# USB-ESP32.net
KiCad netlist of a schematic drawn in Altium Designer
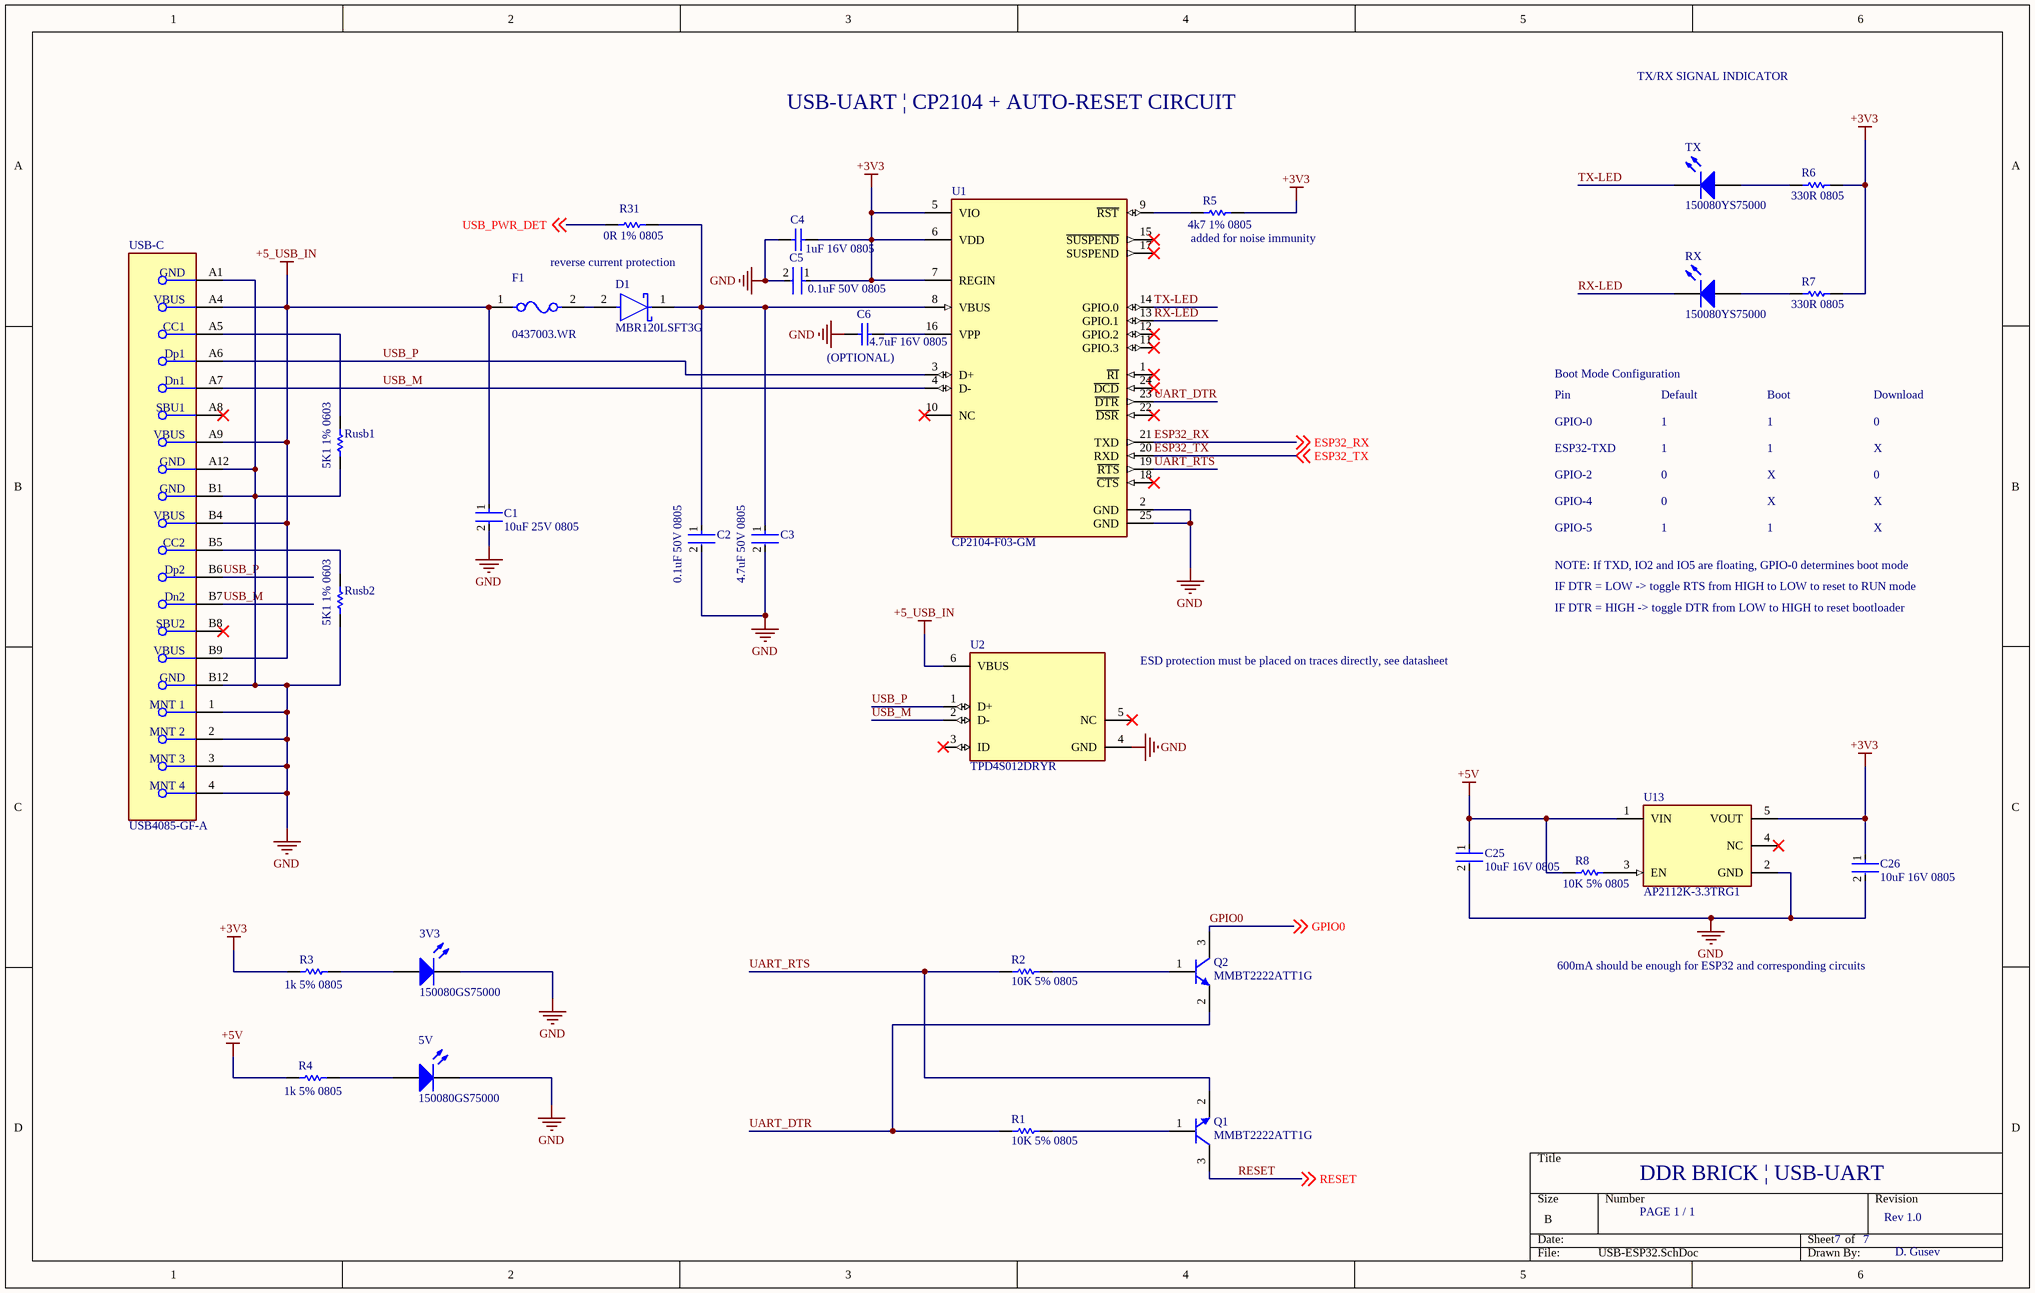
[diagram p0: USB-ESP32.SchDoc]

(export (version "E")
  (design (tool "Eeschema 10.0.6"))
  (components
    (comp (ref "3V3")
      (value "150080GS75000")
      (footprint "0805_A")
      (description "SMD mono-color Chip LED, WL-SMCW, Green")
      (fields (field (name "MANUFACTURER") "Wuerth Elektronik"))
      (libsource (lib "Altium Content Vault") (part "WE-LED_K1A2-2"))
    )
    (comp (ref "5V")
      (value "150080GS75000")
      (footprint "0805_A")
      (description "SMD mono-color Chip LED, WL-SMCW, Green")
      (fields (field (name "MANUFACTURER") "Wuerth Elektronik"))
      (libsource (lib "Altium Content Vault") (part "WE-LED_K1A2-2"))
    )
    (comp (ref "C1")
      (value "10uF 25V 0805")
      (footprint "FP-GRM21B-0_15-IPC_C")
      (description "Chip Multilayer Ceramic Capacitors for General Purpose, 0805, 10uF, X5R, 15%, 10%, 25V")
      (fields (field (name "VOLTAGE") "25V") (field (name "TOLERANCE") "10%"))
      (libsource (lib "Altium Content Vault") (part "b4654b650e69147ec39a6b967a45e02"))
    )
    (comp (ref "C2")
      (value "0.1uF 50V 0805")
      (footprint "FP-C0805C-DN-MFG")
      (description "CAP CER 0.1UF 50V X7R 0805")
      (fields
        (field (name "MANUFACTURER PART NUMBER") "C0805C104K5RACTU")
        (field (name "MANUFACTURER") "KEMET")
      )
      (libsource (lib "Altium Content Vault") (part "b4654b650e69147ec39a6b967a45e02"))
    )
    (comp (ref "C3")
      (value "4.7uF 50V 0805")
      (footprint "FP-C2012-125-MFG")
      (description "CAP CER 4.7UF 50V X5R 0805")
      (fields
        (field (name "TOLERANCE") "10%")
        (field (name "MANUFACTURER PART NUMBER") "C2012X5R1H475K125AB")
      )
      (libsource (lib "Altium Content Vault") (part "11868f565c42a9108669ba33697ecf6"))
    )
    (comp (ref "C4")
      (value "1uF 16V 0805")
      (footprint "CAPC2013X145X50LL20T25")
      (fields (field (name "MANUFACTURER") "Kemet") (field (name "PART NUMBER") "C0805C105K4PACTU"))
      (libsource (lib "Altium Content Vault") (part "CAP"))
    )
    (comp (ref "C5")
      (value "0.1uF 50V 0805")
      (footprint "FP-C0805C-DN-MFG")
      (description "CAP CER 0.1UF 50V X7R 0805")
      (fields
        (field (name "MANUFACTURER PART NUMBER") "C0805C104K5RACTU")
        (field (name "MANUFACTURER") "KEMET")
      )
      (libsource (lib "Altium Content Vault") (part "b4654b650e69147ec39a6b967a45e02"))
    )
    (comp (ref "C6")
      (value "4.7uF 16V 0805")
      (footprint "CAPC2013X140X50LL20T25")
      (fields (field (name "PART NUMBER") "C0805C475K4PACTU") (field (name "MANUFACTURER") "Kemet"))
      (libsource (lib "Altium Content Vault") (part "CAP"))
    )
    (comp (ref "C25")
      (value "10uF 16V 0805")
      (footprint "FP-GRM21B-0_1-IPC_C")
      (description "Chip Multilayer Ceramic Capacitors for General Purpose, 0805, 10uF, X5R, 15%, 10%, 16V")
      (fields (field (name "TOLERANCE") "10%") (field (name "VOLTAGE") "16V"))
      (libsource (lib "Altium Content Vault") (part "b4654b650e69147ec39a6b967a45e02"))
    )
    (comp (ref "C26")
      (value "10uF 16V 0805")
      (footprint "FP-GRM21B-0_1-IPC_C")
      (description "Chip Multilayer Ceramic Capacitors for General Purpose, 0805, 10uF, X5R, 15%, 10%, 16V")
      (fields (field (name "TOLERANCE") "10%") (field (name "VOLTAGE") "16V"))
      (libsource (lib "Altium Content Vault") (part "b4654b650e69147ec39a6b967a45e02"))
    )
    (comp (ref "D1")
      (value "MBR120LSFT3G")
      (footprint "FP-498-MFG")
      (description "DIODE SCHOTTKY 20V 1A SOD123L")
      (libsource (lib "Altium Content Vault") (part "1d6ec82d83fb6aee721767c19dac4b9"))
    )
    (comp (ref "F1")
      (value "0437003.WR")
      (footprint "FP-437-MFG")
      (description "FUSE BRD MNT 3A 32VAC 35VDC 1206")
      (fields
        (field (name "OCTOPART") "https://octopart.com/0437003.wr-littelfuse-8600121")
        (field (name "MANUFACTURER") "Littelfuse Inc")
      )
      (libsource (lib "Altium Content Vault") (part "5bcf9b9f640e542cf0359d10258e979"))
    )
    (comp (ref "Q1")
      (value "MMBT2222ATT1G")
      (footprint "ONSC-SC-75-3-463-01_V")
      (description "General Purpose Transistor, NPN Silicon, 3-Pin SC-75, Pb-Free, Tape and Reel")
      (fields (field (name "MANUFACTURER") "On Semiconductor"))
      (libsource (lib "Altium Content Vault") (part "ONSC-NPN-B1E2C3-3"))
    )
    (comp (ref "Q2")
      (value "MMBT2222ATT1G")
      (footprint "ONSC-SC-75-3-463-01_V")
      (description "General Purpose Transistor, NPN Silicon, 3-Pin SC-75, Pb-Free, Tape and Reel")
      (fields (field (name "MANUFACTURER") "On Semiconductor"))
      (libsource (lib "Altium Content Vault") (part "ONSC-NPN-B1E2C3-3"))
    )
    (comp (ref "R1")
      (value "10K 5% 0805")
      (footprint "RESC2013X60X40ML20T25")
      (fields (field (name "PART NUMBER") "ERA6AEB123V") (field (name "MANUFACTURER") "Panasonic"))
      (libsource (lib "Altium Content Vault") (part "RES"))
    )
    (comp (ref "R2")
      (value "10K 5% 0805")
      (footprint "RESC2013X60X40ML20T25")
      (fields (field (name "PART NUMBER") "ERA6AEB123V") (field (name "MANUFACTURER") "Panasonic"))
      (libsource (lib "Altium Content Vault") (part "RES"))
    )
    (comp (ref "R3")
      (value "1k 5% 0805")
      (footprint "RESC2013X60X35ML10T20")
      (description "Chip Resistor, 1 KOhm, +/- 1%, 125 mW, -55 to 155 degC, 0805 (2012 Metric), RoHS, Tape and Reel")
      (fields (field (name "TOLERANCE") "1%") (field (name "MANUFACTURER") "Yageo"))
      (libsource (lib "Altium Content Vault") (part "RES-2"))
    )
    (comp (ref "R4")
      (value "1k 5% 0805")
      (footprint "RESC2013X60X35ML10T20")
      (description "Chip Resistor, 1 KOhm, +/- 1%, 125 mW, -55 to 155 degC, 0805 (2012 Metric), RoHS, Tape and Reel")
      (fields (field (name "TOLERANCE") "1%") (field (name "MANUFACTURER") "Yageo"))
      (libsource (lib "Altium Content Vault") (part "RES-2"))
    )
    (comp (ref "R5")
      (value "4k7 1% 0805")
      (footprint "YAGO-RC0805_M")
      (fields
        (field (name "TOLERANCE") "+/- 1%")
        (field (name "PARTNUMBER") "RC0805FR-074K7L")
        (field (name "POWER") "0.125 W")
      )
      (libsource (lib "Altium Content Vault") (part "YAGO-RES-2"))
    )
    (comp (ref "R6")
      (value "330R 0805")
      (footprint "RESC2013X60X35LL10T20")
      (description "Chip Resistor, 330 Ohm, +/- 1%, 125 mW, -55 to 155 degC, 0805 (2012 Metric), RoHS, Tape and Reel")
      (fields (field (name "MANUFACTURER") "Yageo") (field (name "TOLERANCE") "1%"))
      (libsource (lib "Altium Content Vault") (part "RES-2"))
    )
    (comp (ref "R7")
      (value "330R 0805")
      (footprint "RESC2013X60X35LL10T20")
      (description "Chip Resistor, 330 Ohm, +/- 1%, 125 mW, -55 to 155 degC, 0805 (2012 Metric), RoHS, Tape and Reel")
      (fields (field (name "MANUFACTURER") "Yageo") (field (name "TOLERANCE") "1%"))
      (libsource (lib "Altium Content Vault") (part "RES-2"))
    )
    (comp (ref "R8")
      (value "10K 5% 0805")
      (footprint "RESC2013X60X40ML20T25")
      (fields (field (name "PART NUMBER") "ERA6AEB123V") (field (name "MANUFACTURER") "Panasonic"))
      (libsource (lib "Altium Content Vault") (part "RES"))
    )
    (comp (ref "R31")
      (value "0R 1% 0805")
      (footprint "RESC2013X60X35ML10T20")
      (fields (field (name "TOLERANCE") "5%") (field (name "MANUFACTURER") "Yageo"))
      (libsource (lib "Altium Content Vault") (part "RES-2"))
    )
    (comp (ref "Rusb1")
      (value "5K1 1% 0603")
      (footprint "RESC1608X55X25ML10T15")
      (fields (field (name "MANUFACTURER") "Yageo") (field (name "PART NUMBER") "RC0603FR-075K1L"))
      (libsource (lib "Altium Content Vault") (part "RES"))
    )
    (comp (ref "Rusb2")
      (value "5K1 1% 0603")
      (footprint "RESC1608X55X25ML10T15")
      (fields (field (name "MANUFACTURER") "Yageo") (field (name "PART NUMBER") "RC0603FR-075K1L"))
      (libsource (lib "Altium Content Vault") (part "RES"))
    )
    (comp (ref "RX")
      (value "150080YS75000")
      (footprint "0805_A")
      (description "SMD mono-color Chip LED, WL-SMCW, Yellow")
      (fields (field (name "MANUFACTURER") "Wuerth Elektronik"))
      (libsource (lib "Altium Content Vault") (part "WE-LED_K1A2-2"))
    )
    (comp (ref "TX")
      (value "150080YS75000")
      (footprint "0805_A")
      (description "SMD mono-color Chip LED, WL-SMCW, Yellow")
      (fields (field (name "MANUFACTURER") "Wuerth Elektronik"))
      (libsource (lib "Altium Content Vault") (part "WE-LED_K1A2-2"))
    )
    (comp (ref "U1")
      (value "CP2104-F03-GM")
      (footprint "FP-CP2104-F03-GM-MFG")
      (description "IC SGL USB-TO-UART BRIDGE 24QFN")
      (libsource (lib "Altium Content Vault") (part "36aa9e967c7f1036f799a443da3d357"))
    )
    (comp (ref "U2")
      (value "TPD4S012DRYR")
      (footprint "FP-DRY0006A-MFG")
      (description "TVS DIODE 5.5V 6SON")
      (libsource (lib "Altium Content Vault") (part "0f51f1bc734c3fed0021f16fcfaf2e1"))
    )
    (comp (ref "U13")
      (value "AP2112K-3.3TRG1")
      (footprint "FP-SOT25-IPC_A")
      (description "IC REG LINEAR 3.3V 600MA SOT25")
      (libsource (lib "Altium Content Vault") (part "c8ab751aee5229183125ab046a11caa"))
    )
    (comp (ref "USB-C")
      (value "USB4085-GF-A")
      (footprint "FP-USB4085-GF-A-MFG")
      (description "CONN RCPT USB2.0 TYPEC 16POS")
      (fields
        (field (name "MANUFACTURER") "Global Connector Technology")
        (field (name "OCTOPART") "https://octopart.com/usb4085-gf-a-global+connector+technology-94773699")
      )
      (libsource (lib "Altium Content Vault") (part "f6997dba88850a18107ac0013977506"))
    )
  )
  (nets
    (net (code "1") (name "+3V3") (class "Default")
      (node (ref "C26") (pin "1") (pinfunction "1_1") (pintype "passive"))
      (node (ref "C4") (pin "2") (pinfunction "2_2") (pintype "passive"))
      (node (ref "C5") (pin "1") (pinfunction "1_1") (pintype "passive"))
      (node (ref "R3") (pin "1") (pinfunction "1_1") (pintype "passive"))
      (node (ref "R5") (pin "2") (pinfunction "2_2") (pintype "passive"))
      (node (ref "R6") (pin "2") (pinfunction "2_2") (pintype "passive"))
      (node (ref "R7") (pin "2") (pinfunction "2_2") (pintype "passive"))
      (node (ref "U1") (pin "5") (pinfunction "VIO_5") (pintype "power_in"))
      (node (ref "U1") (pin "6") (pinfunction "VDD_6") (pintype "power_in"))
      (node (ref "U1") (pin "7") (pinfunction "REGIN_7") (pintype "power_in"))
      (node (ref "U13") (pin "5") (pinfunction "VOUT_5") (pintype "power_in"))
    )
    (net (code "2") (name "+5V") (class "Default")
      (node (ref "C25") (pin "1") (pinfunction "1_1") (pintype "passive"))
      (node (ref "R4") (pin "1") (pinfunction "1_1") (pintype "passive"))
      (node (ref "R8") (pin "2") (pinfunction "2_2") (pintype "passive"))
      (node (ref "U13") (pin "1") (pinfunction "VIN_1") (pintype "power_in"))
    )
    (net (code "3") (name "+5_USB_IN") (class "Default")
      (node (ref "C1") (pin "1") (pinfunction "1_1") (pintype "passive"))
      (node (ref "F1") (pin "1") (pinfunction "1_1") (pintype "passive"))
      (node (ref "U2") (pin "6") (pinfunction "VBUS_6") (pintype "passive"))
      (node (ref "USB-C") (pin "A4") (pinfunction "VBUS_A4") (pintype "power_in"))
      (node (ref "USB-C") (pin "A9") (pinfunction "VBUS_A9") (pintype "power_in"))
      (node (ref "USB-C") (pin "B4") (pinfunction "VBUS_B4") (pintype "power_in"))
      (node (ref "USB-C") (pin "B9") (pinfunction "VBUS_B9") (pintype "power_in"))
    )
    (net (code "4") (name "/RX-LED") (class "Default")
      (node (ref "RX") (pin "1") (pinfunction "K_1") (pintype "passive"))
      (node (ref "U1") (pin "13") (pinfunction "GPIO.1_13") (pintype "bidirectional"))
    )
    (net (code "5") (name "/TX-LED") (class "Default")
      (node (ref "TX") (pin "1") (pinfunction "K_1") (pintype "passive"))
      (node (ref "U1") (pin "14") (pinfunction "GPIO.0_14") (pintype "bidirectional"))
    )
    (net (code "6") (name "/UART_DTR") (class "Default")
      (node (ref "Q2") (pin "2") (pinfunction "E_2") (pintype "passive"))
      (node (ref "R1") (pin "2") (pinfunction "2_2") (pintype "passive"))
      (node (ref "U1") (pin "23") (pinfunction "~{DTR}_23") (pintype "output"))
    )
    (net (code "7") (name "/UART_RTS") (class "Default")
      (node (ref "Q1") (pin "2") (pinfunction "E_2") (pintype "passive"))
      (node (ref "R2") (pin "2") (pinfunction "2_2") (pintype "passive"))
      (node (ref "U1") (pin "19") (pinfunction "~{RTS}_19") (pintype "output"))
    )
    (net (code "8") (name "/USB_M") (class "Default")
      (node (ref "U1") (pin "4") (pinfunction "D-_4") (pintype "bidirectional"))
      (node (ref "U2") (pin "2") (pinfunction "D-_2") (pintype "bidirectional"))
      (node (ref "USB-C") (pin "A7") (pinfunction "Dn1_A7") (pintype "passive"))
      (node (ref "USB-C") (pin "B7") (pinfunction "Dn2_B7") (pintype "passive"))
    )
    (net (code "9") (name "/USB_P") (class "Default")
      (node (ref "U1") (pin "3") (pinfunction "D+_3") (pintype "bidirectional"))
      (node (ref "U2") (pin "1") (pinfunction "D+_1") (pintype "bidirectional"))
      (node (ref "USB-C") (pin "A6") (pinfunction "Dp1_A6") (pintype "passive"))
      (node (ref "USB-C") (pin "B6") (pinfunction "Dp2_B6") (pintype "passive"))
    )
    (net (code "10") (name "ESP32_RX") (class "Default")
      (node (ref "U1") (pin "21") (pinfunction "TXD_21") (pintype "output"))
    )
    (net (code "11") (name "ESP32_TX") (class "Default")
      (node (ref "U1") (pin "20") (pinfunction "RXD_20") (pintype "input"))
    )
    (net (code "12") (name "GND") (class "Default")
      (node (ref "3V3") (pin "1") (pinfunction "K_1") (pintype "passive"))
      (node (ref "5V") (pin "1") (pinfunction "K_1") (pintype "passive"))
      (node (ref "C1") (pin "2") (pinfunction "2_2") (pintype "passive"))
      (node (ref "C2") (pin "2") (pinfunction "2_2") (pintype "passive"))
      (node (ref "C25") (pin "2") (pinfunction "2_2") (pintype "passive"))
      (node (ref "C26") (pin "2") (pinfunction "2_2") (pintype "passive"))
      (node (ref "C3") (pin "2") (pinfunction "2_2") (pintype "passive"))
      (node (ref "C4") (pin "1") (pinfunction "1_1") (pintype "passive"))
      (node (ref "C5") (pin "2") (pinfunction "2_2") (pintype "passive"))
      (node (ref "C6") (pin "2") (pinfunction "2_2") (pintype "passive"))
      (node (ref "Rusb1") (pin "1") (pinfunction "1_1") (pintype "passive"))
      (node (ref "Rusb2") (pin "1") (pinfunction "1_1") (pintype "passive"))
      (node (ref "U1") (pin "2") (pinfunction "GND_2") (pintype "power_in"))
      (node (ref "U1") (pin "25") (pinfunction "GND_25") (pintype "power_in"))
      (node (ref "U13") (pin "2") (pinfunction "GND_2") (pintype "power_in"))
      (node (ref "U2") (pin "4") (pinfunction "GND_4") (pintype "power_in"))
      (node (ref "USB-C") (pin "1") (pinfunction "MNT_1_1") (pintype "passive"))
      (node (ref "USB-C") (pin "2") (pinfunction "MNT_2_2") (pintype "passive"))
      (node (ref "USB-C") (pin "3") (pinfunction "MNT_3_3") (pintype "passive"))
      (node (ref "USB-C") (pin "4") (pinfunction "MNT_4_4") (pintype "passive"))
      (node (ref "USB-C") (pin "A1") (pinfunction "GND_A1") (pintype "power_in"))
      (node (ref "USB-C") (pin "A12") (pinfunction "GND_A12") (pintype "power_in"))
      (node (ref "USB-C") (pin "B1") (pinfunction "GND_B1") (pintype "power_in"))
      (node (ref "USB-C") (pin "B12") (pinfunction "GND_B12") (pintype "power_in"))
    )
    (net (code "13") (name "GPIO0") (class "Default")
      (node (ref "Q2") (pin "3") (pinfunction "C_3") (pintype "passive"))
    )
    (net (code "14") (name "Net-(3V3-A)") (class "Default")
      (node (ref "3V3") (pin "2") (pinfunction "A_2") (pintype "passive"))
      (node (ref "R3") (pin "2") (pinfunction "2_2") (pintype "passive"))
    )
    (net (code "15") (name "Net-(5V-A)") (class "Default")
      (node (ref "5V") (pin "2") (pinfunction "A_2") (pintype "passive"))
      (node (ref "R4") (pin "2") (pinfunction "2_2") (pintype "passive"))
    )
    (net (code "16") (name "Net-(D1-A)") (class "Default")
      (node (ref "D1") (pin "2") (pinfunction "A_2") (pintype "passive"))
      (node (ref "F1") (pin "2") (pinfunction "2_2") (pintype "passive"))
    )
    (net (code "17") (name "Net-(D1-C)") (class "Default")
      (node (ref "C2") (pin "1") (pinfunction "1_1") (pintype "passive"))
      (node (ref "C3") (pin "1") (pinfunction "1_1") (pintype "passive"))
      (node (ref "D1") (pin "1") (pinfunction "C_1") (pintype "passive"))
      (node (ref "R31") (pin "2") (pinfunction "2_2") (pintype "passive"))
      (node (ref "U1") (pin "8") (pinfunction "VBUS_8") (pintype "input"))
    )
    (net (code "18") (name "Net-(Q1-B)") (class "Default")
      (node (ref "Q1") (pin "1") (pinfunction "B_1") (pintype "passive"))
      (node (ref "R1") (pin "1") (pinfunction "1_1") (pintype "passive"))
    )
    (net (code "19") (name "Net-(Q2-B)") (class "Default")
      (node (ref "Q2") (pin "1") (pinfunction "B_1") (pintype "passive"))
      (node (ref "R2") (pin "1") (pinfunction "1_1") (pintype "passive"))
    )
    (net (code "20") (name "Net-(RX-A)") (class "Default")
      (node (ref "R7") (pin "1") (pinfunction "1_1") (pintype "passive"))
      (node (ref "RX") (pin "2") (pinfunction "A_2") (pintype "passive"))
    )
    (net (code "21") (name "Net-(TX-A)") (class "Default")
      (node (ref "R6") (pin "1") (pinfunction "1_1") (pintype "passive"))
      (node (ref "TX") (pin "2") (pinfunction "A_2") (pintype "passive"))
    )
    (net (code "22") (name "Net-(U1-VPP)") (class "Default")
      (node (ref "C6") (pin "1") (pinfunction "1_1") (pintype "passive"))
      (node (ref "U1") (pin "16") (pinfunction "VPP_16") (pintype "passive"))
    )
    (net (code "23") (name "Net-(U1-~{RST})") (class "Default")
      (node (ref "R5") (pin "1") (pinfunction "1_1") (pintype "passive"))
      (node (ref "U1") (pin "9") (pinfunction "~{RST}_9") (pintype "bidirectional"))
    )
    (net (code "24") (name "Net-(U13-EN)") (class "Default")
      (node (ref "R8") (pin "1") (pinfunction "1_1") (pintype "passive"))
      (node (ref "U13") (pin "3") (pinfunction "EN_3") (pintype "input"))
    )
    (net (code "25") (name "Net-(USB-C-CC1)") (class "Default")
      (node (ref "Rusb1") (pin "2") (pinfunction "2_2") (pintype "passive"))
      (node (ref "USB-C") (pin "A5") (pinfunction "CC1_A5") (pintype "passive"))
    )
    (net (code "26") (name "Net-(USB-C-CC2)") (class "Default")
      (node (ref "Rusb2") (pin "2") (pinfunction "2_2") (pintype "passive"))
      (node (ref "USB-C") (pin "B5") (pinfunction "CC2_B5") (pintype "passive"))
    )
    (net (code "27") (name "RESET") (class "Default")
      (node (ref "Q1") (pin "3") (pinfunction "C_3") (pintype "passive"))
    )
    (net (code "28") (name "USB_PWR_DET") (class "Default")
      (node (ref "R31") (pin "1") (pinfunction "1_1") (pintype "passive"))
    )
    (net (code "29") (name "unconnected-(U1-GPIO.2-Pad12)") (class "Default")
      (node (ref "U1") (pin "12") (pinfunction "GPIO.2_12") (pintype "bidirectional+no_connect"))
    )
    (net (code "30") (name "unconnected-(U1-GPIO.3-Pad11)") (class "Default")
      (node (ref "U1") (pin "11") (pinfunction "GPIO.3_11") (pintype "bidirectional+no_connect"))
    )
    (net (code "31") (name "unconnected-(U1-NC-Pad10)") (class "Default")
      (node (ref "U1") (pin "10") (pinfunction "NC_10") (pintype "passive+no_connect"))
    )
    (net (code "32") (name "unconnected-(U1-SUSPEND-Pad17)") (class "Default")
      (node (ref "U1") (pin "17") (pinfunction "SUSPEND_17") (pintype "output+no_connect"))
    )
    (net (code "33") (name "unconnected-(U1-~{CTS}-Pad18)") (class "Default")
      (node (ref "U1") (pin "18") (pinfunction "~{CTS}_18") (pintype "input+no_connect"))
    )
    (net (code "34") (name "unconnected-(U1-~{DCD}-Pad24)") (class "Default")
      (node (ref "U1") (pin "24") (pinfunction "~{DCD}_24") (pintype "input+no_connect"))
    )
    (net (code "35") (name "unconnected-(U1-~{DSR}-Pad22)") (class "Default")
      (node (ref "U1") (pin "22") (pinfunction "~{DSR}_22") (pintype "input+no_connect"))
    )
    (net (code "36") (name "unconnected-(U1-~{RI}-Pad1)") (class "Default")
      (node (ref "U1") (pin "1") (pinfunction "~{RI}_1") (pintype "input+no_connect"))
    )
    (net (code "37") (name "unconnected-(U1-~{SUSPEND}-Pad15)") (class "Default")
      (node (ref "U1") (pin "15") (pinfunction "~{SUSPEND}_15") (pintype "output+no_connect"))
    )
    (net (code "38") (name "unconnected-(U2-ID-Pad3)") (class "Default")
      (node (ref "U2") (pin "3") (pinfunction "ID_3") (pintype "bidirectional+no_connect"))
    )
    (net (code "39") (name "unconnected-(U2-NC-Pad5)") (class "Default")
      (node (ref "U2") (pin "5") (pinfunction "NC_5") (pintype "passive+no_connect"))
    )
    (net (code "40") (name "unconnected-(U13-NC-Pad4)") (class "Default")
      (node (ref "U13") (pin "4") (pinfunction "NC_4") (pintype "passive+no_connect"))
    )
    (net (code "41") (name "unconnected-(USB-C-SBU1-PadA8)") (class "Default")
      (node (ref "USB-C") (pin "A8") (pinfunction "SBU1_A8") (pintype "passive+no_connect"))
    )
    (net (code "42") (name "unconnected-(USB-C-SBU2-PadB8)") (class "Default")
      (node (ref "USB-C") (pin "B8") (pinfunction "SBU2_B8") (pintype "passive+no_connect"))
    )
  )
)
